# Side_Panel_Experement_-_6_cells.net
KiCad netlist of a schematic drawn in EAGLE
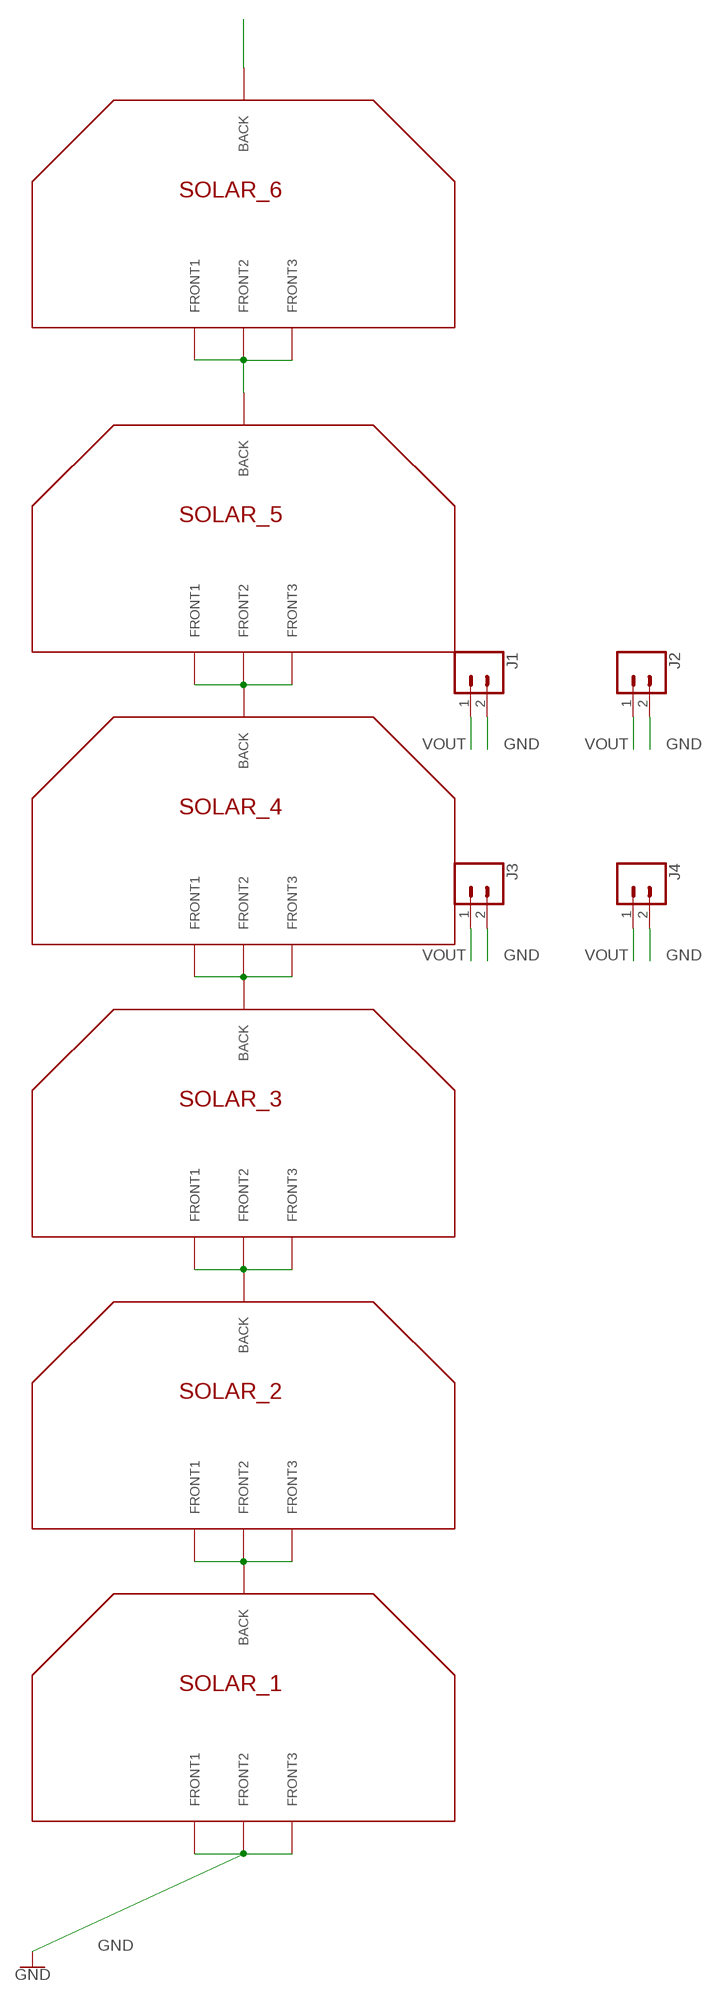
[diagram p0: schematic, sheet 1]

(export (version "E")
  (design (tool "Eeschema 10.0.6"))
  (components
    (comp (ref "J1")
      (value "CONN_02")
      (footprint "eagle-import:1X02")
      (libsource (lib "eagle-import") (part "CONN_02"))
    )
    (comp (ref "J2")
      (value "CONN_02")
      (footprint "eagle-import:1X02")
      (libsource (lib "eagle-import") (part "CONN_02"))
    )
    (comp (ref "J3")
      (value "CONN_02")
      (footprint "eagle-import:1X02")
      (libsource (lib "eagle-import") (part "CONN_02"))
    )
    (comp (ref "J4")
      (value "CONN_02")
      (footprint "eagle-import:1X02")
      (libsource (lib "eagle-import") (part "CONN_02"))
    )
    (comp (ref "SOLAR_1")
      (value "SOLAR_CELL_HALF_TABSFULL_TABS")
      (footprint "eagle-import:SOLAR_CELL_3G30A_FULL_TABS")
      (libsource (lib "eagle-import") (part "SOLAR_CELL_HALF_TABSFULL_TABS"))
    )
    (comp (ref "SOLAR_2")
      (value "SOLAR_CELL_HALF_TABSFULL_TABS")
      (footprint "eagle-import:SOLAR_CELL_3G30A_FULL_TABS")
      (libsource (lib "eagle-import") (part "SOLAR_CELL_HALF_TABSFULL_TABS"))
    )
    (comp (ref "SOLAR_3")
      (value "SOLAR_CELL_HALF_TABSFULL_TABS")
      (footprint "eagle-import:SOLAR_CELL_3G30A_FULL_TABS")
      (libsource (lib "eagle-import") (part "SOLAR_CELL_HALF_TABSFULL_TABS"))
    )
    (comp (ref "SOLAR_4")
      (value "SOLAR_CELL_HALF_TABSFULL_TABS")
      (footprint "eagle-import:SOLAR_CELL_3G30A_FULL_TABS")
      (libsource (lib "eagle-import") (part "SOLAR_CELL_HALF_TABSFULL_TABS"))
    )
    (comp (ref "SOLAR_5")
      (value "SOLAR_CELL_HALF_TABSFULL_TABS")
      (footprint "eagle-import:SOLAR_CELL_3G30A_FULL_TABS")
      (libsource (lib "eagle-import") (part "SOLAR_CELL_HALF_TABSFULL_TABS"))
    )
    (comp (ref "SOLAR_6")
      (value "SOLAR_CELL_HALF_TABSFULL_TABS")
      (footprint "eagle-import:SOLAR_CELL_3G30A_FULL_TABS")
      (libsource (lib "eagle-import") (part "SOLAR_CELL_HALF_TABSFULL_TABS"))
    )
  )
  (nets
    (net (code "1") (name "/VOUT") (class "Default")
      (node (ref "J1") (pin "1") (pinfunction "1_1") (pintype "passive"))
      (node (ref "J2") (pin "1") (pinfunction "1_1") (pintype "passive"))
      (node (ref "J3") (pin "1") (pinfunction "1_1") (pintype "passive"))
      (node (ref "J4") (pin "1") (pinfunction "1_1") (pintype "passive"))
    )
    (net (code "2") (name "GND") (class "Default")
      (node (ref "J1") (pin "2") (pinfunction "2_2") (pintype "passive"))
      (node (ref "J2") (pin "2") (pinfunction "2_2") (pintype "passive"))
      (node (ref "J3") (pin "2") (pinfunction "2_2") (pintype "passive"))
      (node (ref "J4") (pin "2") (pinfunction "2_2") (pintype "passive"))
      (node (ref "SOLAR_1") (pin "P$F1") (pinfunction "FRONT1_P$F1") (pintype "bidirectional"))
      (node (ref "SOLAR_1") (pin "P$F2") (pinfunction "FRONT2_P$F2") (pintype "bidirectional"))
      (node (ref "SOLAR_1") (pin "P$F3") (pinfunction "FRONT3_P$F3") (pintype "bidirectional"))
    )
    (net (code "3") (name "Net-(SOLAR_1-BACK)") (class "Default")
      (node (ref "SOLAR_1") (pin "P$1") (pinfunction "BACK_P$1") (pintype "bidirectional"))
      (node (ref "SOLAR_2") (pin "P$F1") (pinfunction "FRONT1_P$F1") (pintype "bidirectional"))
      (node (ref "SOLAR_2") (pin "P$F2") (pinfunction "FRONT2_P$F2") (pintype "bidirectional"))
      (node (ref "SOLAR_2") (pin "P$F3") (pinfunction "FRONT3_P$F3") (pintype "bidirectional"))
    )
    (net (code "4") (name "Net-(SOLAR_2-BACK)") (class "Default")
      (node (ref "SOLAR_2") (pin "P$1") (pinfunction "BACK_P$1") (pintype "bidirectional"))
      (node (ref "SOLAR_3") (pin "P$F1") (pinfunction "FRONT1_P$F1") (pintype "bidirectional"))
      (node (ref "SOLAR_3") (pin "P$F2") (pinfunction "FRONT2_P$F2") (pintype "bidirectional"))
      (node (ref "SOLAR_3") (pin "P$F3") (pinfunction "FRONT3_P$F3") (pintype "bidirectional"))
    )
    (net (code "5") (name "Net-(SOLAR_3-BACK)") (class "Default")
      (node (ref "SOLAR_3") (pin "P$1") (pinfunction "BACK_P$1") (pintype "bidirectional"))
      (node (ref "SOLAR_4") (pin "P$F1") (pinfunction "FRONT1_P$F1") (pintype "bidirectional"))
      (node (ref "SOLAR_4") (pin "P$F2") (pinfunction "FRONT2_P$F2") (pintype "bidirectional"))
      (node (ref "SOLAR_4") (pin "P$F3") (pinfunction "FRONT3_P$F3") (pintype "bidirectional"))
    )
    (net (code "6") (name "Net-(SOLAR_4-BACK)") (class "Default")
      (node (ref "SOLAR_4") (pin "P$1") (pinfunction "BACK_P$1") (pintype "bidirectional"))
      (node (ref "SOLAR_5") (pin "P$F1") (pinfunction "FRONT1_P$F1") (pintype "bidirectional"))
      (node (ref "SOLAR_5") (pin "P$F2") (pinfunction "FRONT2_P$F2") (pintype "bidirectional"))
      (node (ref "SOLAR_5") (pin "P$F3") (pinfunction "FRONT3_P$F3") (pintype "bidirectional"))
    )
    (net (code "7") (name "Net-(SOLAR_5-BACK)") (class "Default")
      (node (ref "SOLAR_5") (pin "P$1") (pinfunction "BACK_P$1") (pintype "bidirectional"))
      (node (ref "SOLAR_6") (pin "P$F1") (pinfunction "FRONT1_P$F1") (pintype "bidirectional"))
      (node (ref "SOLAR_6") (pin "P$F2") (pinfunction "FRONT2_P$F2") (pintype "bidirectional"))
      (node (ref "SOLAR_6") (pin "P$F3") (pinfunction "FRONT3_P$F3") (pintype "bidirectional"))
    )
    (net (code "8") (name "unconnected-(SOLAR_6-BACK-PadP$1)") (class "Default")
      (node (ref "SOLAR_6") (pin "P$1") (pinfunction "BACK_P$1") (pintype "bidirectional"))
    )
  )
)
